# Motor_PI_Hat.net
KiCad netlist of a schematic drawn in EasyEDA
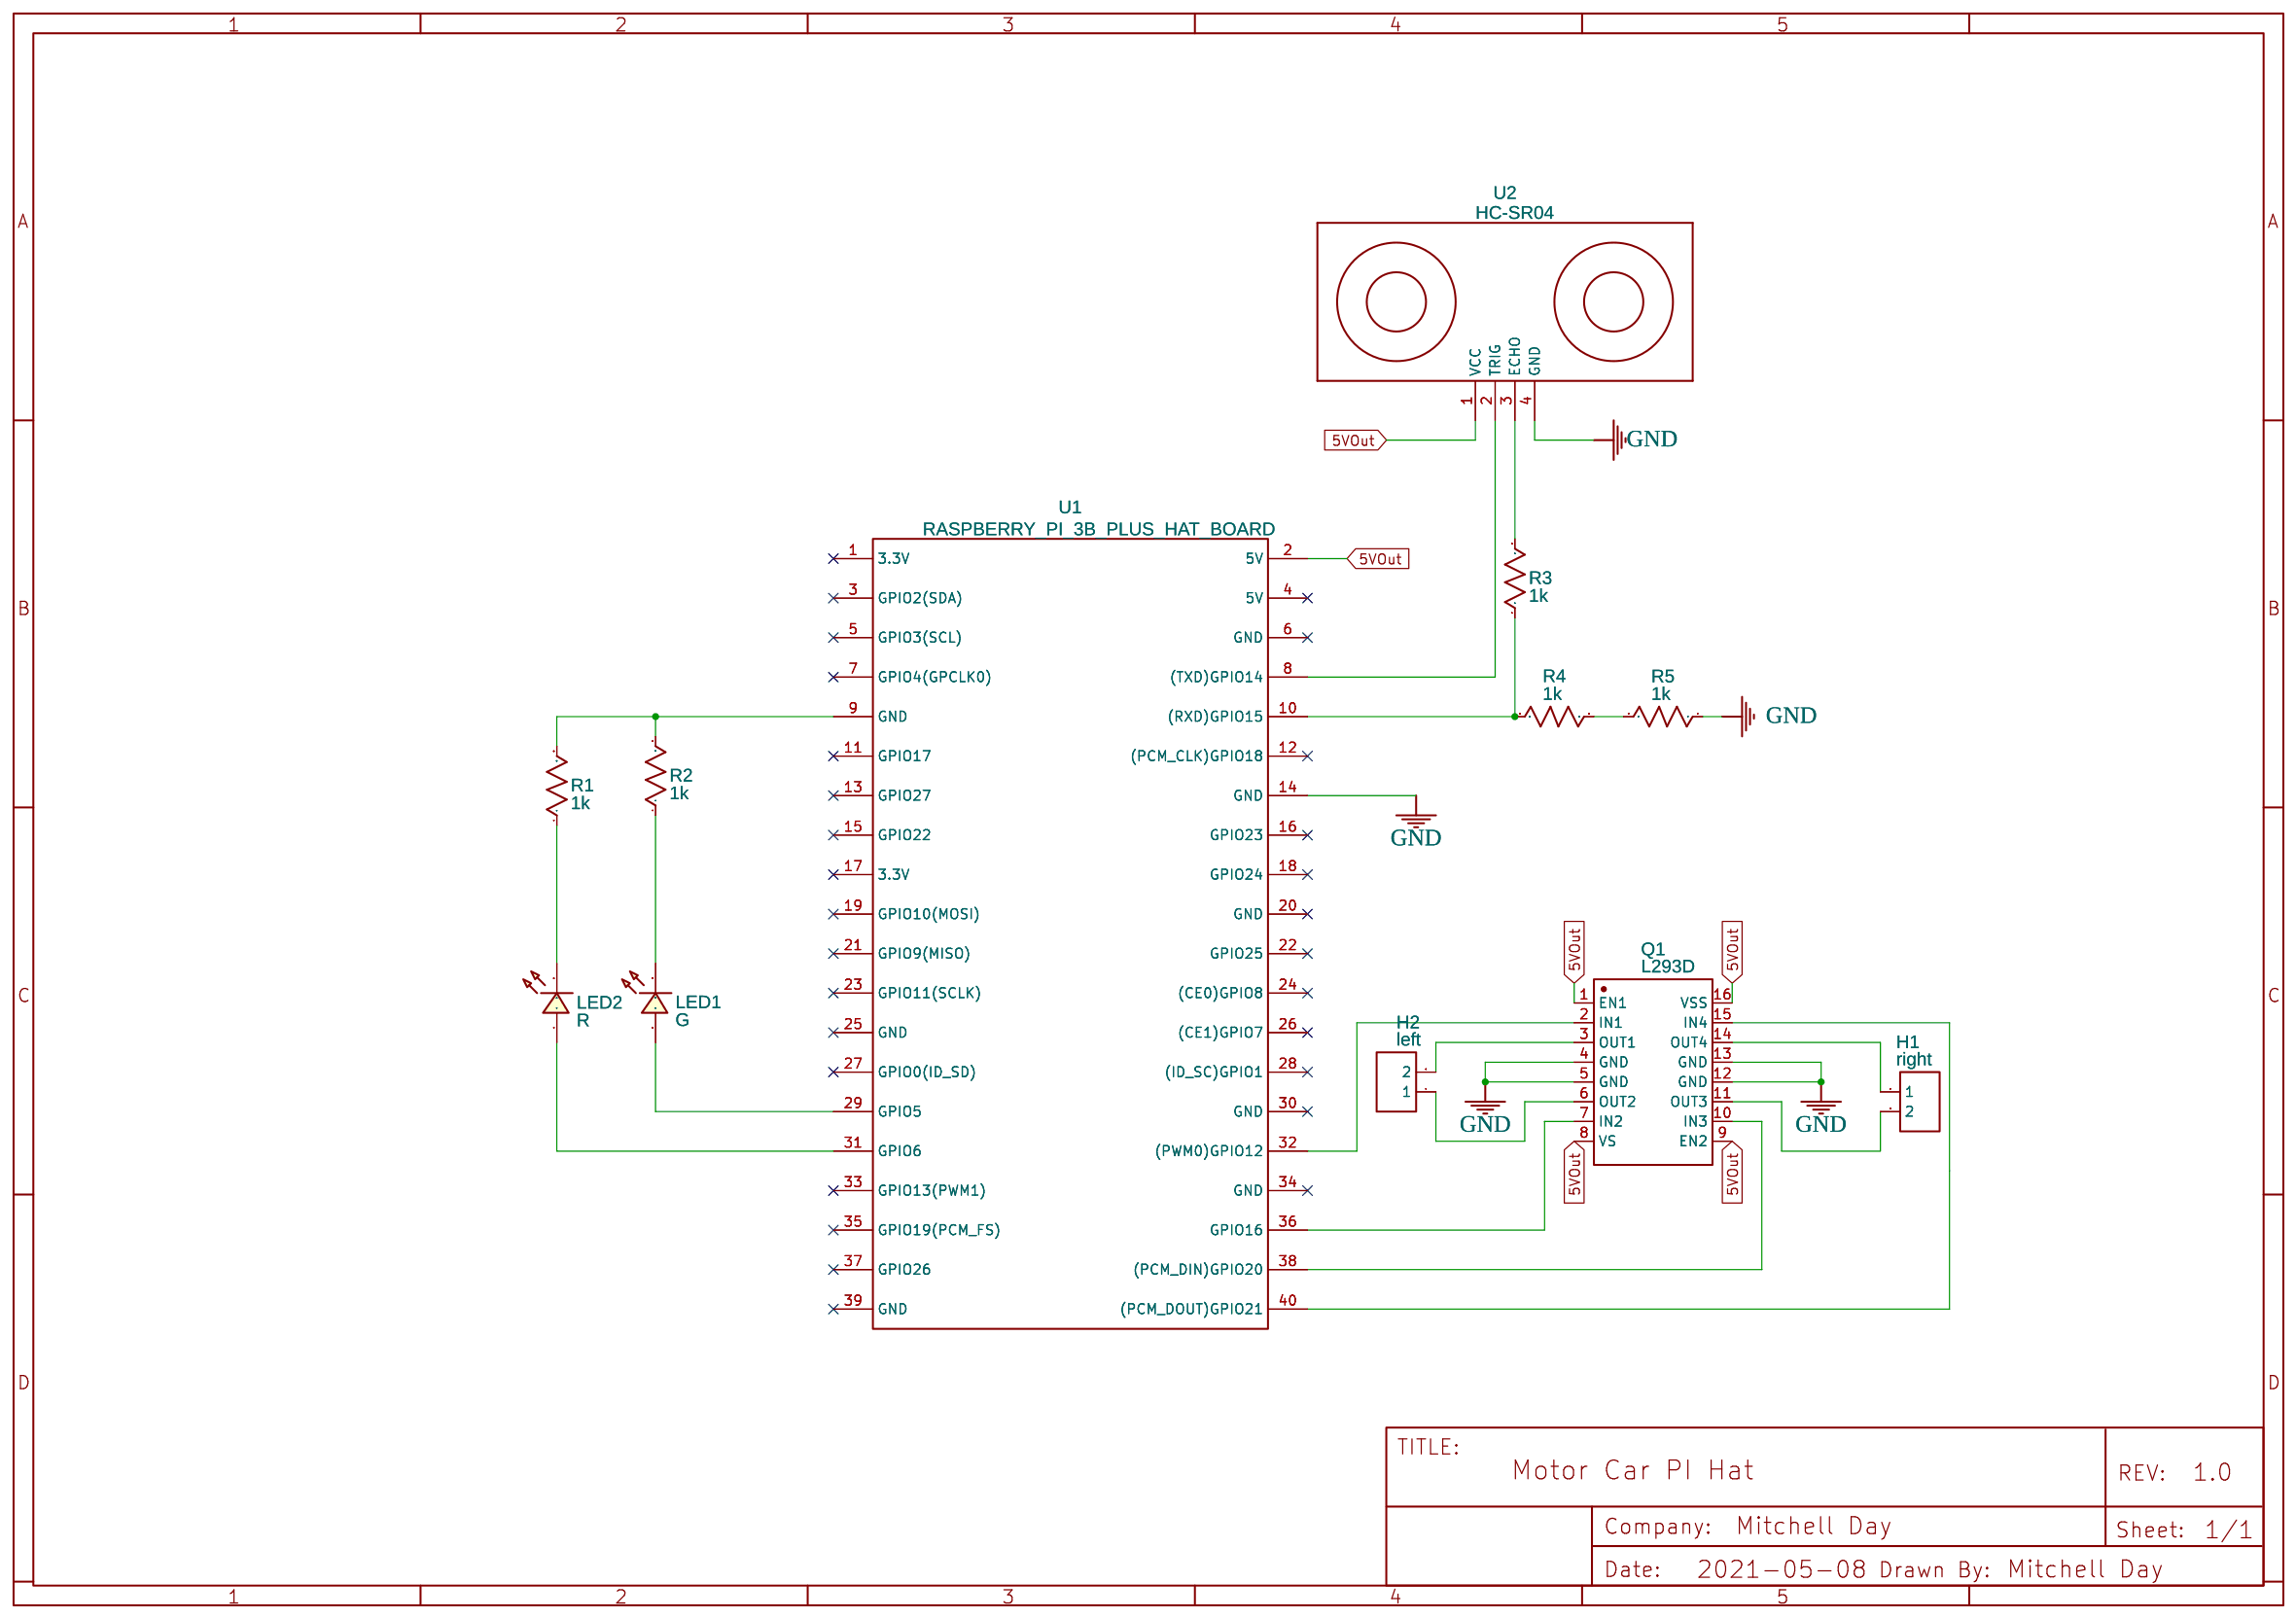
[diagram p0: schematic sheet]

(export (version "E")
  (design (tool "Eeschema 10.0.6"))
  (components
    (comp (ref "H1")
      (value "right")
      (fields (field (name "BOM_Supplier Part") "C49661"))
      (libsource (lib "") (part "HDR-F-2.54_1x2"))
    )
    (comp (ref "H2")
      (value "left")
      (fields (field (name "BOM_Supplier Part") "C49661"))
      (libsource (lib "") (part "HDR-F-2.54_1x2_1"))
    )
    (comp (ref "LED1")
      (value "G")
      (fields
        (field (name "BOM_Manufacturer Part") "204-10SYGD/S530-E3")
        (field (name "BOM_Supplier Part") "C85161")
      )
      (libsource (lib "") (part "LED-TH-3mm_G"))
    )
    (comp (ref "LED2")
      (value "R")
      (fields
        (field (name "BOM_Manufacturer Part") "204-10SDRD/S530-A3-L")
        (field (name "BOM_Supplier Part") "C84774")
      )
      (libsource (lib "") (part "LED-TH-3mm_R"))
    )
    (comp (ref "Q1")
      (value "L293D")
      (fields
        (field (name "BOM_Manufacturer Part") "POWERDIP16")
        (field (name "BOM_Supplier Part") "SGS-THOMSON")
      )
      (libsource (lib "") (part "L293D"))
    )
    (comp (ref "R1") (value "1k") (libsource (lib "") (part "R_AXIAL-0.3_US_1")))
    (comp (ref "R2") (value "1k") (libsource (lib "") (part "R_AXIAL-0.3_US_1")))
    (comp (ref "R3") (value "1k") (libsource (lib "") (part "R_AXIAL-0.3_US_1")))
    (comp (ref "R4") (value "1k") (libsource (lib "") (part "R_AXIAL-0.3_US")))
    (comp (ref "R5") (value "1k") (libsource (lib "") (part "R_AXIAL-0.3_US")))
    (comp (ref "U1")
      (value "RASPBERRY_PI_3B_PLUS_HAT_BOARD")
      (fields (field (name "BOM_Manufacturer Part") "Raspberry-Pi-3B-Plus-HAT-Board"))
      (libsource (lib "") (part "RASPBERRY_PI_3B_PLUS_HAT_BOARD"))
    )
    (comp (ref "U2") (value "HC-SR04") (libsource (lib "") (part "HC-SR04")))
  )
  (nets
    (net (code "1") (name "5VOut") (class "Default")
      (node (ref "Q1") (pin "1") (pinfunction "EN1_1") (pintype "unspecified"))
      (node (ref "Q1") (pin "16") (pinfunction "VSS_16") (pintype "unspecified"))
      (node (ref "Q1") (pin "8") (pinfunction "VS_8") (pintype "unspecified"))
      (node (ref "Q1") (pin "9") (pinfunction "EN2_9") (pintype "unspecified"))
      (node (ref "U1") (pin "2") (pinfunction "5V_2") (pintype "unspecified"))
      (node (ref "U2") (pin "1") (pinfunction "VCC_1") (pintype "passive"))
    )
    (net (code "2") (name "GND") (class "Default")
      (node (ref "Q1") (pin "12") (pinfunction "GND_12") (pintype "unspecified"))
      (node (ref "Q1") (pin "13") (pinfunction "GND_13") (pintype "unspecified"))
      (node (ref "Q1") (pin "4") (pinfunction "GND_4") (pintype "unspecified"))
      (node (ref "Q1") (pin "5") (pinfunction "GND_5") (pintype "unspecified"))
      (node (ref "R5") (pin "1") (pinfunction "1_1") (pintype "unspecified"))
      (node (ref "U1") (pin "14") (pinfunction "GND_14") (pintype "unspecified"))
      (node (ref "U2") (pin "4") (pinfunction "GND_4") (pintype "passive"))
    )
    (net (code "3") (name "Net-(LED1-Pad2)") (class "Default")
      (node (ref "LED1") (pin "2") (pinfunction "2_2") (pintype "unspecified"))
      (node (ref "R2") (pin "1") (pinfunction "1_1") (pintype "unspecified"))
    )
    (net (code "4") (name "Net-(LED2-Pad2)") (class "Default")
      (node (ref "LED2") (pin "2") (pinfunction "2_2") (pintype "unspecified"))
      (node (ref "R1") (pin "1") (pinfunction "1_1") (pintype "unspecified"))
    )
    (net (code "5") (name "Net-(Q1-IN1)") (class "Default")
      (node (ref "Q1") (pin "2") (pinfunction "IN1_2") (pintype "unspecified"))
      (node (ref "U1") (pin "32") (pinfunction "(PWM0)GPIO12_32") (pintype "unspecified"))
    )
    (net (code "6") (name "Net-(Q1-IN2)") (class "Default")
      (node (ref "Q1") (pin "7") (pinfunction "IN2_7") (pintype "unspecified"))
      (node (ref "U1") (pin "36") (pinfunction "GPIO16_36") (pintype "unspecified"))
    )
    (net (code "7") (name "Net-(Q1-IN3)") (class "Default")
      (node (ref "Q1") (pin "10") (pinfunction "IN3_10") (pintype "unspecified"))
      (node (ref "U1") (pin "38") (pinfunction "(PCM_DIN)GPIO20_38") (pintype "unspecified"))
    )
    (net (code "8") (name "Net-(Q1-IN4)") (class "Default")
      (node (ref "Q1") (pin "15") (pinfunction "IN4_15") (pintype "unspecified"))
      (node (ref "U1") (pin "40") (pinfunction "(PCM_DOUT)GPIO21_40") (pintype "unspecified"))
    )
    (net (code "9") (name "Net-(Q1-OUT1)") (class "Default")
      (node (ref "H2") (pin "2") (pinfunction "2_2") (pintype "input"))
      (node (ref "Q1") (pin "3") (pinfunction "OUT1_3") (pintype "unspecified"))
    )
    (net (code "10") (name "Net-(Q1-OUT2)") (class "Default")
      (node (ref "H2") (pin "1") (pinfunction "1_1") (pintype "input"))
      (node (ref "Q1") (pin "6") (pinfunction "OUT2_6") (pintype "unspecified"))
    )
    (net (code "11") (name "Net-(Q1-OUT3)") (class "Default")
      (node (ref "H1") (pin "2") (pinfunction "2_2") (pintype "input"))
      (node (ref "Q1") (pin "11") (pinfunction "OUT3_11") (pintype "unspecified"))
    )
    (net (code "12") (name "Net-(Q1-OUT4)") (class "Default")
      (node (ref "H1") (pin "1") (pinfunction "1_1") (pintype "input"))
      (node (ref "Q1") (pin "14") (pinfunction "OUT4_14") (pintype "unspecified"))
    )
    (net (code "13") (name "Net-(R1-Pad2)") (class "Default")
      (node (ref "R1") (pin "2") (pinfunction "2_2") (pintype "unspecified"))
      (node (ref "R2") (pin "2") (pinfunction "2_2") (pintype "unspecified"))
      (node (ref "U1") (pin "9") (pinfunction "GND_9") (pintype "unspecified"))
    )
    (net (code "14") (name "Net-(R4-Pad1)") (class "Default")
      (node (ref "R4") (pin "1") (pinfunction "1_1") (pintype "unspecified"))
      (node (ref "R5") (pin "2") (pinfunction "2_2") (pintype "unspecified"))
    )
    (net (code "15") (name "Net-(U1-(RXD)GPIO15)") (class "Default")
      (node (ref "R3") (pin "1") (pinfunction "1_1") (pintype "unspecified"))
      (node (ref "R4") (pin "2") (pinfunction "2_2") (pintype "unspecified"))
      (node (ref "U1") (pin "10") (pinfunction "(RXD)GPIO15_10") (pintype "unspecified"))
    )
    (net (code "16") (name "Net-(U1-(TXD)GPIO14)") (class "Default")
      (node (ref "U1") (pin "8") (pinfunction "(TXD)GPIO14_8") (pintype "unspecified"))
      (node (ref "U2") (pin "2") (pinfunction "TRIG_2") (pintype "input"))
    )
    (net (code "17") (name "Net-(U1-GPIO5)") (class "Default")
      (node (ref "LED1") (pin "1") (pinfunction "1_1") (pintype "unspecified"))
      (node (ref "U1") (pin "29") (pinfunction "GPIO5_29") (pintype "unspecified"))
    )
    (net (code "18") (name "Net-(U1-GPIO6)") (class "Default")
      (node (ref "LED2") (pin "1") (pinfunction "1_1") (pintype "unspecified"))
      (node (ref "U1") (pin "31") (pinfunction "GPIO6_31") (pintype "unspecified"))
    )
    (net (code "19") (name "Net-(U2-ECHO)") (class "Default")
      (node (ref "R3") (pin "2") (pinfunction "2_2") (pintype "unspecified"))
      (node (ref "U2") (pin "3") (pinfunction "ECHO_3") (pintype "output"))
    )
    (net (code "20") (name "unconnected-(U1-(CE0)GPIO8-Pad24)") (class "Default")
      (node (ref "U1") (pin "24") (pinfunction "(CE0)GPIO8_24") (pintype "unspecified+no_connect"))
    )
    (net (code "21") (name "unconnected-(U1-(CE1)GPIO7-Pad26)") (class "Default")
      (node (ref "U1") (pin "26") (pinfunction "(CE1)GPIO7_26") (pintype "unspecified+no_connect"))
    )
    (net (code "22") (name "unconnected-(U1-(ID_SC)GPIO1-Pad28)") (class "Default")
      (node (ref "U1") (pin "28") (pinfunction "(ID_SC)GPIO1_28") (pintype "unspecified+no_connect"))
    )
    (net (code "23") (name "unconnected-(U1-(PCM_CLK)GPIO18-Pad12)") (class "Default")
      (node (ref "U1") (pin "12") (pinfunction "(PCM_CLK)GPIO18_12") (pintype "unspecified+no_connect"))
    )
    (net (code "24") (name "unconnected-(U1-3.3V-Pad1)") (class "Default")
      (node (ref "U1") (pin "1") (pinfunction "3.3V_1") (pintype "unspecified+no_connect"))
    )
    (net (code "25") (name "unconnected-(U1-3.3V-Pad17)") (class "Default")
      (node (ref "U1") (pin "17") (pinfunction "3.3V_17") (pintype "unspecified+no_connect"))
    )
    (net (code "26") (name "unconnected-(U1-5V-Pad4)") (class "Default")
      (node (ref "U1") (pin "4") (pinfunction "5V_4") (pintype "unspecified+no_connect"))
    )
    (net (code "27") (name "unconnected-(U1-GND-Pad6)") (class "Default")
      (node (ref "U1") (pin "6") (pinfunction "GND_6") (pintype "unspecified+no_connect"))
    )
    (net (code "28") (name "unconnected-(U1-GND-Pad20)") (class "Default")
      (node (ref "U1") (pin "20") (pinfunction "GND_20") (pintype "unspecified+no_connect"))
    )
    (net (code "29") (name "unconnected-(U1-GND-Pad25)") (class "Default")
      (node (ref "U1") (pin "25") (pinfunction "GND_25") (pintype "unspecified+no_connect"))
    )
    (net (code "30") (name "unconnected-(U1-GND-Pad30)") (class "Default")
      (node (ref "U1") (pin "30") (pinfunction "GND_30") (pintype "unspecified+no_connect"))
    )
    (net (code "31") (name "unconnected-(U1-GND-Pad34)") (class "Default")
      (node (ref "U1") (pin "34") (pinfunction "GND_34") (pintype "unspecified+no_connect"))
    )
    (net (code "32") (name "unconnected-(U1-GND-Pad39)") (class "Default")
      (node (ref "U1") (pin "39") (pinfunction "GND_39") (pintype "unspecified+no_connect"))
    )
    (net (code "33") (name "unconnected-(U1-GPIO0(ID_SD)-Pad27)") (class "Default")
      (node (ref "U1") (pin "27") (pinfunction "GPIO0(ID_SD)_27") (pintype "unspecified+no_connect"))
    )
    (net (code "34") (name "unconnected-(U1-GPIO2(SDA)-Pad3)") (class "Default")
      (node (ref "U1") (pin "3") (pinfunction "GPIO2(SDA)_3") (pintype "unspecified+no_connect"))
    )
    (net (code "35") (name "unconnected-(U1-GPIO3(SCL)-Pad5)") (class "Default")
      (node (ref "U1") (pin "5") (pinfunction "GPIO3(SCL)_5") (pintype "unspecified+no_connect"))
    )
    (net (code "36") (name "unconnected-(U1-GPIO4(GPCLK0)-Pad7)") (class "Default")
      (node (ref "U1") (pin "7") (pinfunction "GPIO4(GPCLK0)_7") (pintype "unspecified+no_connect"))
    )
    (net (code "37") (name "unconnected-(U1-GPIO9(MISO)-Pad21)") (class "Default")
      (node (ref "U1") (pin "21") (pinfunction "GPIO9(MISO)_21") (pintype "unspecified+no_connect"))
    )
    (net (code "38") (name "unconnected-(U1-GPIO10(MOSI)-Pad19)") (class "Default")
      (node (ref "U1") (pin "19") (pinfunction "GPIO10(MOSI)_19") (pintype "unspecified+no_connect"))
    )
    (net (code "39") (name "unconnected-(U1-GPIO11(SCLK)-Pad23)") (class "Default")
      (node (ref "U1") (pin "23") (pinfunction "GPIO11(SCLK)_23") (pintype "unspecified+no_connect"))
    )
    (net (code "40") (name "unconnected-(U1-GPIO13(PWM1)-Pad33)") (class "Default")
      (node (ref "U1") (pin "33") (pinfunction "GPIO13(PWM1)_33") (pintype "unspecified+no_connect"))
    )
    (net (code "41") (name "unconnected-(U1-GPIO17-Pad11)") (class "Default")
      (node (ref "U1") (pin "11") (pinfunction "GPIO17_11") (pintype "unspecified+no_connect"))
    )
    (net (code "42") (name "unconnected-(U1-GPIO19(PCM_FS)-Pad35)") (class "Default")
      (node (ref "U1") (pin "35") (pinfunction "GPIO19(PCM_FS)_35") (pintype "unspecified+no_connect"))
    )
    (net (code "43") (name "unconnected-(U1-GPIO22-Pad15)") (class "Default")
      (node (ref "U1") (pin "15") (pinfunction "GPIO22_15") (pintype "unspecified+no_connect"))
    )
    (net (code "44") (name "unconnected-(U1-GPIO23-Pad16)") (class "Default")
      (node (ref "U1") (pin "16") (pinfunction "GPIO23_16") (pintype "unspecified+no_connect"))
    )
    (net (code "45") (name "unconnected-(U1-GPIO24-Pad18)") (class "Default")
      (node (ref "U1") (pin "18") (pinfunction "GPIO24_18") (pintype "unspecified+no_connect"))
    )
    (net (code "46") (name "unconnected-(U1-GPIO25-Pad22)") (class "Default")
      (node (ref "U1") (pin "22") (pinfunction "GPIO25_22") (pintype "unspecified+no_connect"))
    )
    (net (code "47") (name "unconnected-(U1-GPIO26-Pad37)") (class "Default")
      (node (ref "U1") (pin "37") (pinfunction "GPIO26_37") (pintype "unspecified+no_connect"))
    )
    (net (code "48") (name "unconnected-(U1-GPIO27-Pad13)") (class "Default")
      (node (ref "U1") (pin "13") (pinfunction "GPIO27_13") (pintype "unspecified+no_connect"))
    )
  )
)
